# picox_1_1.net
KiCad netlist of a schematic drawn in EAGLE
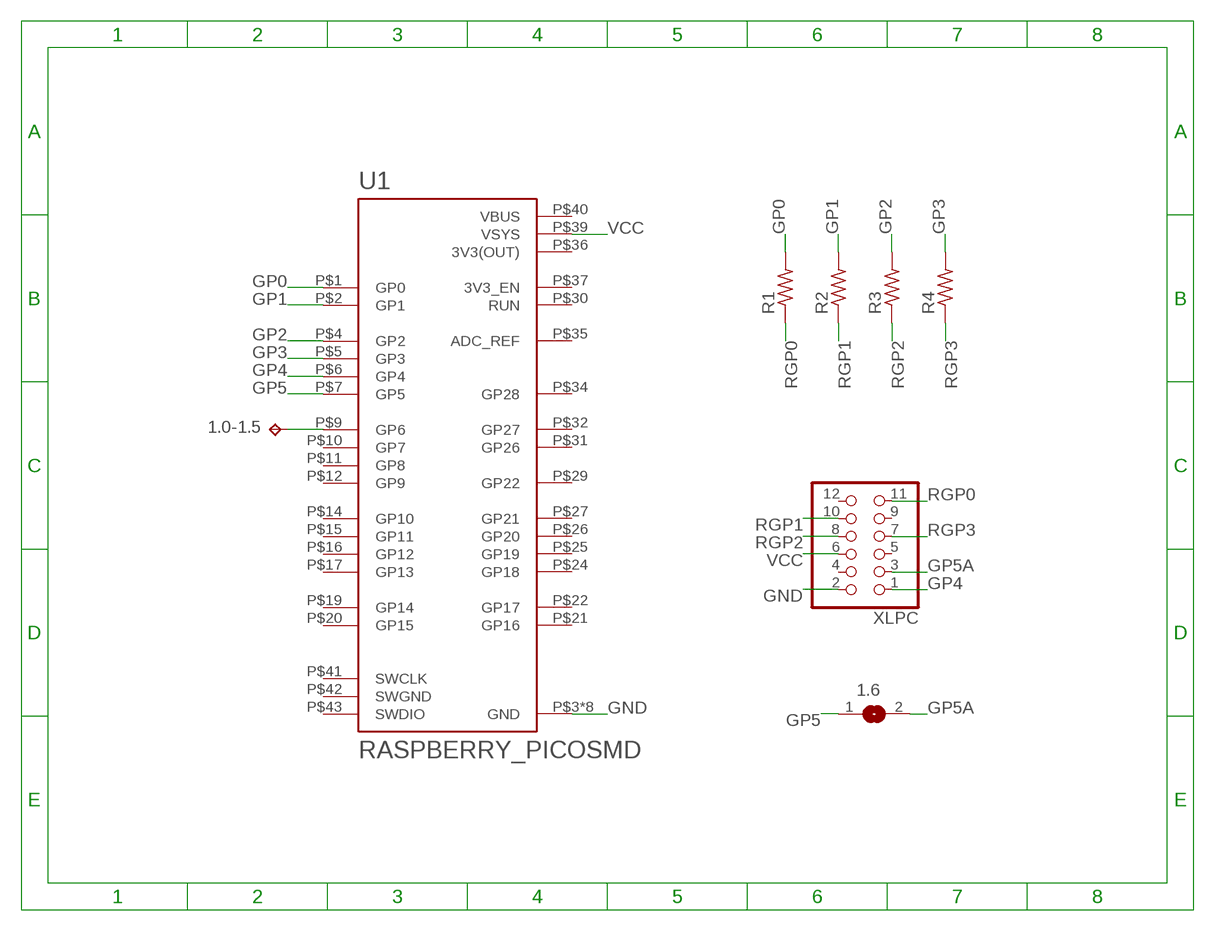
[diagram p0: schematic, sheet 1]

(export (version "E")
  (design (tool "Eeschema 10.0.6"))
  (components
    (comp (ref "1.0-1.5")
      (value "TPTP16SQ")
      (footprint "eagle-import:TP16SQ")
      (libsource (lib "eagle-import") (part "TPTP16SQ"))
    )
    (comp (ref "1.6") (value "SJ") (footprint "eagle-import:SJ") (libsource (lib "eagle-import") (part "SJ")))
    (comp (ref "R1")
      (value "R-US_R0805")
      (footprint "eagle-import:R0805")
      (libsource (lib "eagle-import") (part "R-US_R0805"))
    )
    (comp (ref "R2")
      (value "R-US_R0805")
      (footprint "eagle-import:R0805")
      (libsource (lib "eagle-import") (part "R-US_R0805"))
    )
    (comp (ref "R3")
      (value "R-US_R0805")
      (footprint "eagle-import:R0805")
      (libsource (lib "eagle-import") (part "R-US_R0805"))
    )
    (comp (ref "R4")
      (value "R-US_R0805")
      (footprint "eagle-import:R0805")
      (libsource (lib "eagle-import") (part "R-US_R0805"))
    )
    (comp (ref "U1")
      (value "RASPBERRY_PICOSMD")
      (footprint "eagle-import:PICO-PKG-SMD")
      (libsource (lib "eagle-import") (part "RASPBERRY_PICOSMD"))
    )
    (comp (ref "XLPC")
      (value "PINHD-2X6")
      (footprint "eagle-import:2X06")
      (libsource (lib "eagle-import") (part "PINHD-2X6"))
    )
  )
  (nets
    (net (code "1") (name "/3V3(OUT)") (class "Default")
      (node (ref "U1") (pin "P$36") (pinfunction "3V3(OUT)_P$36") (pintype "power_in"))
    )
    (net (code "2") (name "/GND") (class "Default")
      (node (ref "U1") (pin "P$13") (pinfunction "GND_P$13") (pintype "power_in"))
      (node (ref "U1") (pin "P$18") (pinfunction "GND_P$18") (pintype "power_in"))
      (node (ref "U1") (pin "P$23") (pinfunction "GND_P$23") (pintype "power_in"))
      (node (ref "U1") (pin "P$28") (pinfunction "GND_P$28") (pintype "power_in"))
      (node (ref "U1") (pin "P$3") (pinfunction "GND_P$3") (pintype "power_in"))
      (node (ref "U1") (pin "P$33") (pinfunction "GND_P$33") (pintype "power_in"))
      (node (ref "U1") (pin "P$38") (pinfunction "GND_P$38") (pintype "power_in"))
      (node (ref "U1") (pin "P$8") (pinfunction "GND_P$8") (pintype "power_in"))
      (node (ref "XLPC") (pin "2") (pinfunction "2_2") (pintype "passive"))
    )
    (net (code "3") (name "/GP0") (class "Default")
      (node (ref "R1") (pin "2") (pinfunction "2_2") (pintype "passive"))
      (node (ref "U1") (pin "P$1") (pinfunction "GP0_P$1") (pintype "bidirectional"))
    )
    (net (code "4") (name "/GP1") (class "Default")
      (node (ref "R2") (pin "2") (pinfunction "2_2") (pintype "passive"))
      (node (ref "U1") (pin "P$2") (pinfunction "GP1_P$2") (pintype "bidirectional"))
    )
    (net (code "5") (name "/GP2") (class "Default")
      (node (ref "R3") (pin "2") (pinfunction "2_2") (pintype "passive"))
      (node (ref "U1") (pin "P$4") (pinfunction "GP2_P$4") (pintype "bidirectional"))
    )
    (net (code "6") (name "/GP3") (class "Default")
      (node (ref "R4") (pin "2") (pinfunction "2_2") (pintype "passive"))
      (node (ref "U1") (pin "P$5") (pinfunction "GP3_P$5") (pintype "bidirectional"))
    )
    (net (code "7") (name "/GP4") (class "Default")
      (node (ref "U1") (pin "P$6") (pinfunction "GP4_P$6") (pintype "bidirectional"))
      (node (ref "XLPC") (pin "1") (pinfunction "1_1") (pintype "passive"))
    )
    (net (code "8") (name "/GP5") (class "Default")
      (node (ref "1.6") (pin "1") (pinfunction "1_1") (pintype "passive"))
      (node (ref "U1") (pin "P$7") (pinfunction "GP5_P$7") (pintype "bidirectional"))
    )
    (net (code "9") (name "/GP5A") (class "Default")
      (node (ref "1.6") (pin "2") (pinfunction "2_2") (pintype "passive"))
      (node (ref "XLPC") (pin "3") (pinfunction "3_3") (pintype "passive"))
    )
    (net (code "10") (name "/RGP0") (class "Default")
      (node (ref "R1") (pin "1") (pinfunction "1_1") (pintype "passive"))
      (node (ref "XLPC") (pin "11") (pinfunction "11_11") (pintype "passive"))
    )
    (net (code "11") (name "/RGP1") (class "Default")
      (node (ref "R2") (pin "1") (pinfunction "1_1") (pintype "passive"))
      (node (ref "XLPC") (pin "10") (pinfunction "10_10") (pintype "passive"))
    )
    (net (code "12") (name "/RGP2") (class "Default")
      (node (ref "R3") (pin "1") (pinfunction "1_1") (pintype "passive"))
      (node (ref "XLPC") (pin "8") (pinfunction "8_8") (pintype "passive"))
    )
    (net (code "13") (name "/RGP3") (class "Default")
      (node (ref "R4") (pin "1") (pinfunction "1_1") (pintype "passive"))
      (node (ref "XLPC") (pin "7") (pinfunction "7_7") (pintype "passive"))
    )
    (net (code "14") (name "/SWGND") (class "Default")
      (node (ref "U1") (pin "P$42") (pinfunction "SWGND_P$42") (pintype "power_in"))
    )
    (net (code "15") (name "/VBUS") (class "Default")
      (node (ref "U1") (pin "P$40") (pinfunction "VBUS_P$40") (pintype "power_in"))
    )
    (net (code "16") (name "/VCC") (class "Default")
      (node (ref "U1") (pin "P$39") (pinfunction "VSYS_P$39") (pintype "power_in"))
      (node (ref "XLPC") (pin "6") (pinfunction "6_6") (pintype "passive"))
    )
    (net (code "17") (name "Net-(U1-GP6)") (class "Default")
      (node (ref "1.0-1.5") (pin "TP") (pinfunction "TP_TP") (pintype "input"))
      (node (ref "U1") (pin "P$9") (pinfunction "GP6_P$9") (pintype "bidirectional"))
    )
    (net (code "18") (name "unconnected-(U1-3V3_EN-PadP$37)") (class "Default")
      (node (ref "U1") (pin "P$37") (pinfunction "3V3_EN_P$37") (pintype "input"))
    )
    (net (code "19") (name "unconnected-(U1-ADC_REF-PadP$35)") (class "Default")
      (node (ref "U1") (pin "P$35") (pinfunction "ADC_REF_P$35") (pintype "input"))
    )
    (net (code "20") (name "unconnected-(U1-GP7-PadP$10)") (class "Default")
      (node (ref "U1") (pin "P$10") (pinfunction "GP7_P$10") (pintype "bidirectional"))
    )
    (net (code "21") (name "unconnected-(U1-GP8-PadP$11)") (class "Default")
      (node (ref "U1") (pin "P$11") (pinfunction "GP8_P$11") (pintype "bidirectional"))
    )
    (net (code "22") (name "unconnected-(U1-GP9-PadP$12)") (class "Default")
      (node (ref "U1") (pin "P$12") (pinfunction "GP9_P$12") (pintype "bidirectional"))
    )
    (net (code "23") (name "unconnected-(U1-GP10-PadP$14)") (class "Default")
      (node (ref "U1") (pin "P$14") (pinfunction "GP10_P$14") (pintype "bidirectional"))
    )
    (net (code "24") (name "unconnected-(U1-GP11-PadP$15)") (class "Default")
      (node (ref "U1") (pin "P$15") (pinfunction "GP11_P$15") (pintype "bidirectional"))
    )
    (net (code "25") (name "unconnected-(U1-GP12-PadP$16)") (class "Default")
      (node (ref "U1") (pin "P$16") (pinfunction "GP12_P$16") (pintype "bidirectional"))
    )
    (net (code "26") (name "unconnected-(U1-GP13-PadP$17)") (class "Default")
      (node (ref "U1") (pin "P$17") (pinfunction "GP13_P$17") (pintype "bidirectional"))
    )
    (net (code "27") (name "unconnected-(U1-GP14-PadP$19)") (class "Default")
      (node (ref "U1") (pin "P$19") (pinfunction "GP14_P$19") (pintype "bidirectional"))
    )
    (net (code "28") (name "unconnected-(U1-GP15-PadP$20)") (class "Default")
      (node (ref "U1") (pin "P$20") (pinfunction "GP15_P$20") (pintype "bidirectional"))
    )
    (net (code "29") (name "unconnected-(U1-GP16-PadP$21)") (class "Default")
      (node (ref "U1") (pin "P$21") (pinfunction "GP16_P$21") (pintype "bidirectional"))
    )
    (net (code "30") (name "unconnected-(U1-GP17-PadP$22)") (class "Default")
      (node (ref "U1") (pin "P$22") (pinfunction "GP17_P$22") (pintype "bidirectional"))
    )
    (net (code "31") (name "unconnected-(U1-GP18-PadP$24)") (class "Default")
      (node (ref "U1") (pin "P$24") (pinfunction "GP18_P$24") (pintype "bidirectional"))
    )
    (net (code "32") (name "unconnected-(U1-GP19-PadP$25)") (class "Default")
      (node (ref "U1") (pin "P$25") (pinfunction "GP19_P$25") (pintype "bidirectional"))
    )
    (net (code "33") (name "unconnected-(U1-GP20-PadP$26)") (class "Default")
      (node (ref "U1") (pin "P$26") (pinfunction "GP20_P$26") (pintype "bidirectional"))
    )
    (net (code "34") (name "unconnected-(U1-GP21-PadP$27)") (class "Default")
      (node (ref "U1") (pin "P$27") (pinfunction "GP21_P$27") (pintype "bidirectional"))
    )
    (net (code "35") (name "unconnected-(U1-GP22-PadP$29)") (class "Default")
      (node (ref "U1") (pin "P$29") (pinfunction "GP22_P$29") (pintype "bidirectional"))
    )
    (net (code "36") (name "unconnected-(U1-GP26-PadP$31)") (class "Default")
      (node (ref "U1") (pin "P$31") (pinfunction "GP26_P$31") (pintype "bidirectional"))
    )
    (net (code "37") (name "unconnected-(U1-GP27-PadP$32)") (class "Default")
      (node (ref "U1") (pin "P$32") (pinfunction "GP27_P$32") (pintype "bidirectional"))
    )
    (net (code "38") (name "unconnected-(U1-GP28-PadP$34)") (class "Default")
      (node (ref "U1") (pin "P$34") (pinfunction "GP28_P$34") (pintype "bidirectional"))
    )
    (net (code "39") (name "unconnected-(U1-RUN-PadP$30)") (class "Default")
      (node (ref "U1") (pin "P$30") (pinfunction "RUN_P$30") (pintype "input"))
    )
    (net (code "40") (name "unconnected-(U1-SWCLK-PadP$41)") (class "Default")
      (node (ref "U1") (pin "P$41") (pinfunction "SWCLK_P$41") (pintype "input"))
    )
    (net (code "41") (name "unconnected-(U1-SWDIO-PadP$43)") (class "Default")
      (node (ref "U1") (pin "P$43") (pinfunction "SWDIO_P$43") (pintype "bidirectional"))
    )
    (net (code "42") (name "unconnected-(XLPC-Pad4)") (class "Default")
      (node (ref "XLPC") (pin "4") (pinfunction "4_4") (pintype "passive"))
    )
    (net (code "43") (name "unconnected-(XLPC-Pad5)") (class "Default")
      (node (ref "XLPC") (pin "5") (pinfunction "5_5") (pintype "passive"))
    )
    (net (code "44") (name "unconnected-(XLPC-Pad9)") (class "Default")
      (node (ref "XLPC") (pin "9") (pinfunction "9_9") (pintype "passive"))
    )
    (net (code "45") (name "unconnected-(XLPC-Pad12)") (class "Default")
      (node (ref "XLPC") (pin "12") (pinfunction "12_12") (pintype "passive"))
    )
  )
)
